# 17_FPGA_B12_B13_B14_B15.net
KiCad netlist of a schematic drawn in Altium Designer
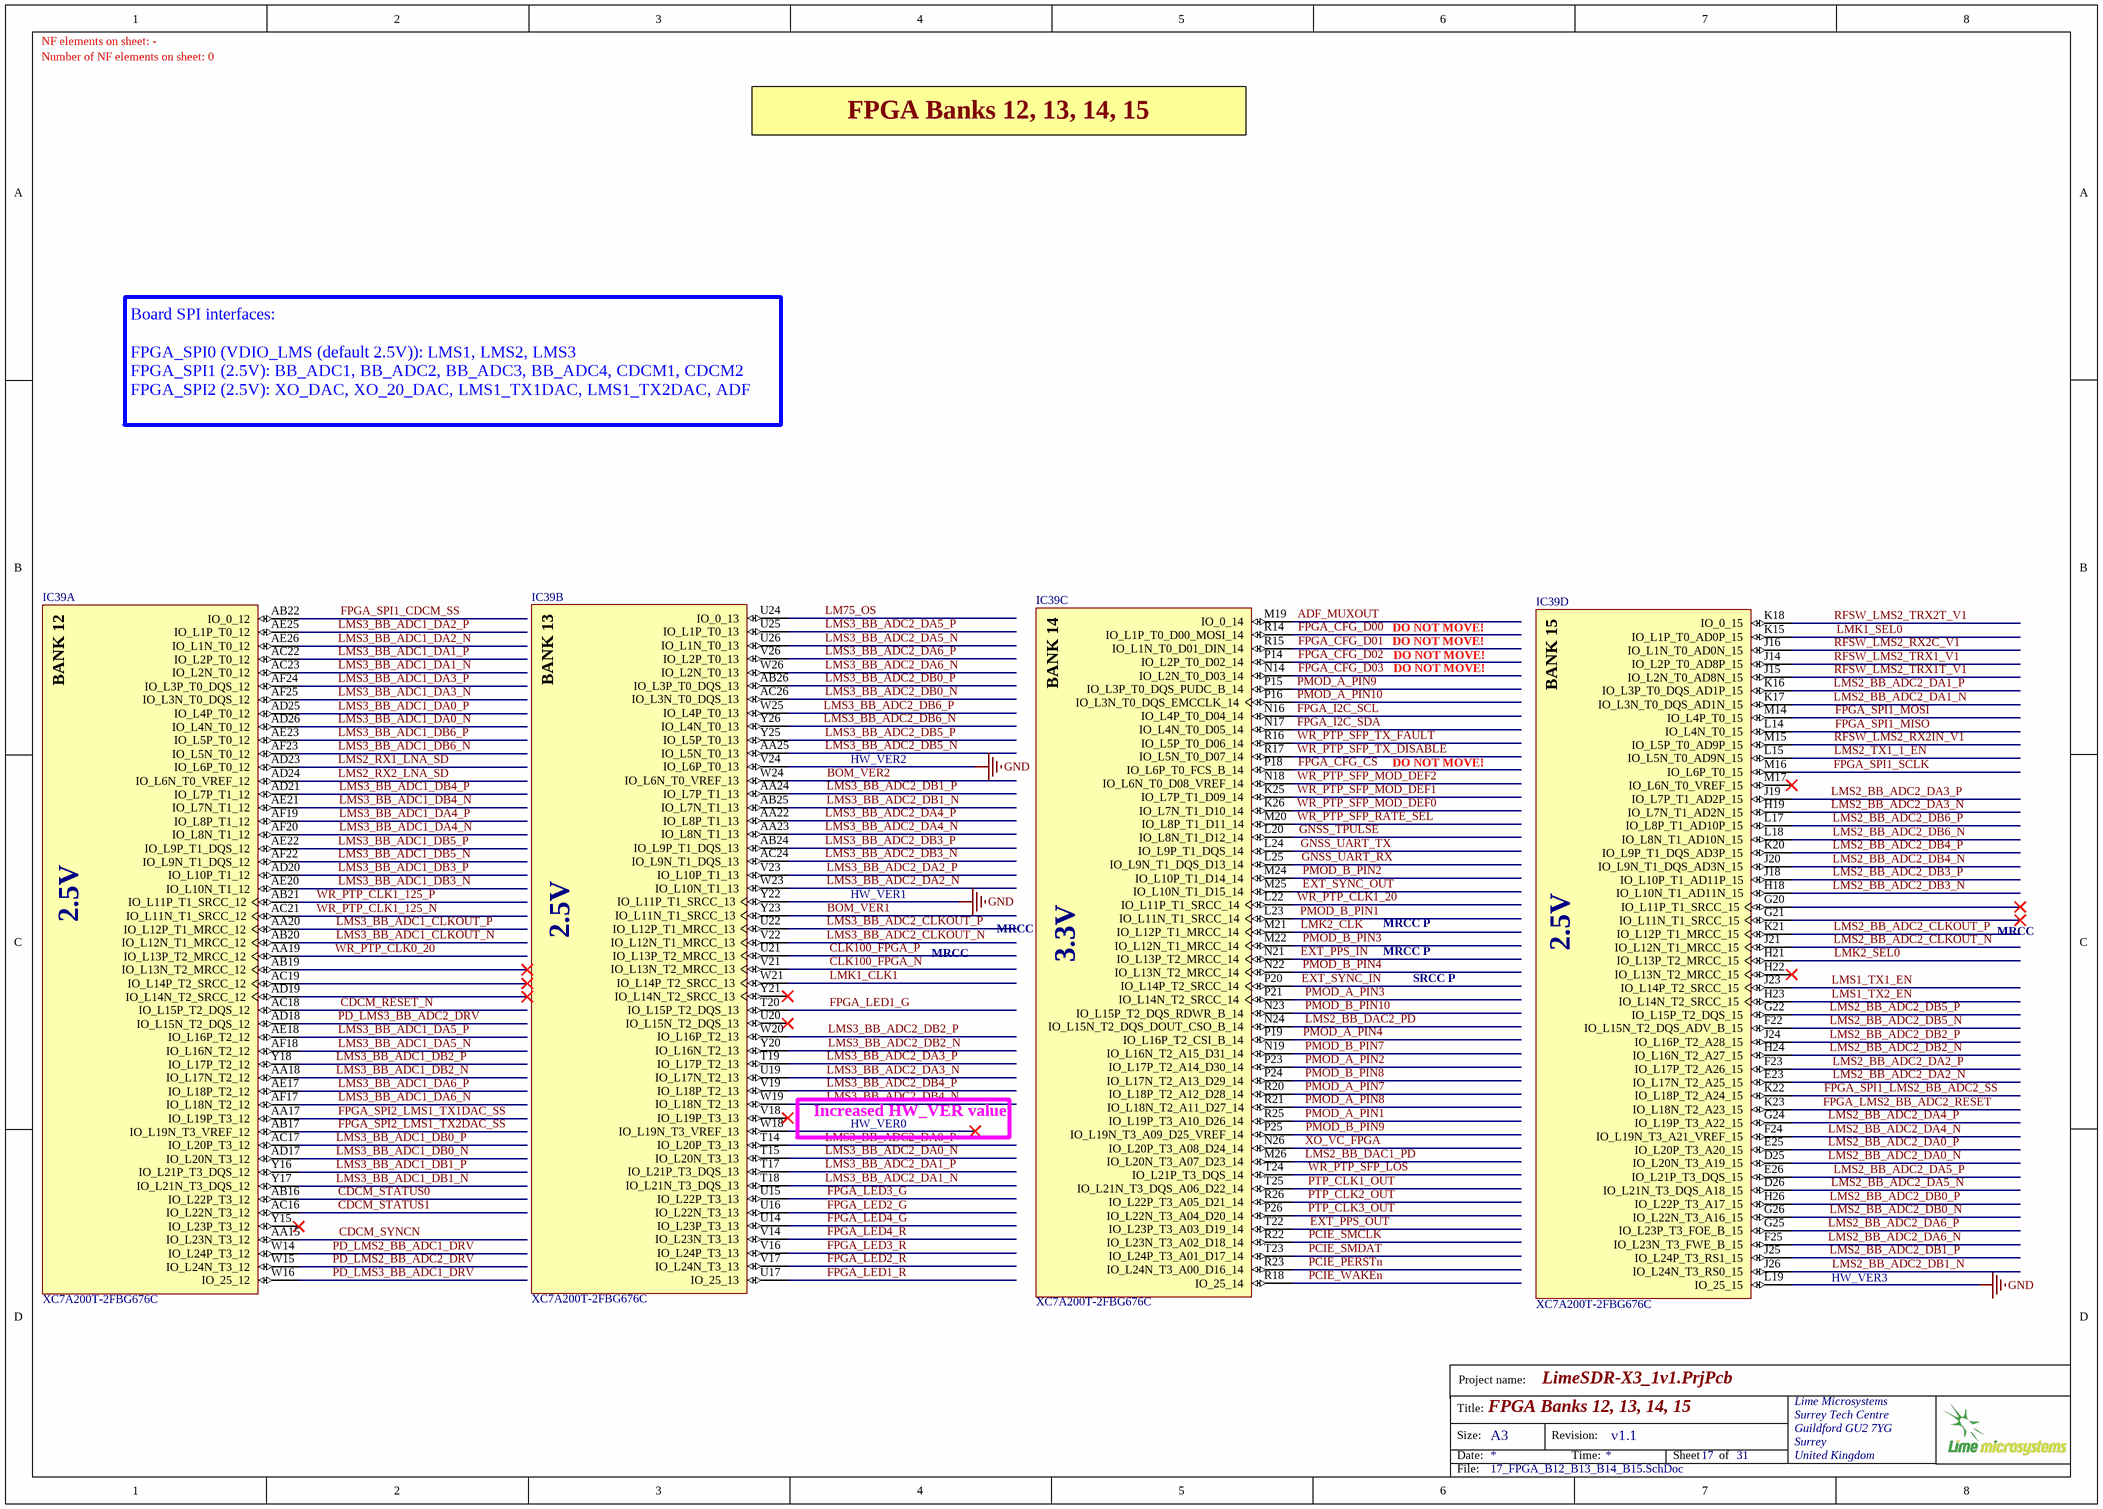
[diagram p0: 17_FPGA_B12_B13_B14_B15.SchDoc]

(export (version "E")
  (design (tool "Eeschema 10.0.6"))
  (components
    (comp (ref "IC39")
      (value "XC7A200T-2FBG676C")
      (footprint "XC7A200T-2FBG676C_FBG676")
      (description "Artix-7 FPGA, 400 User I/Os, 8 GTP, 676-Ball BGA, Speed Grade 2, Commercial Grade, Pb-Free")
      (fields (field (name "MANUFACTURER") "Xilinx"))
      (libsource (lib "LimeMicroAltiumLib_schLib_r02") (part "XC7A200T-2FBG676C"))
    )
  )
  (nets
    (net (code "1") (name "/ADF_MUXOUT") (class "Default")
      (node (ref "IC39") (pin "M19") (pinfunction "IO_0_14_M19") (pintype "bidirectional"))
    )
    (net (code "2") (name "/BOM_VER1") (class "Default")
      (node (ref "IC39") (pin "Y23") (pinfunction "IO_L11N_T1_SRCC_13_Y23") (pintype "bidirectional"))
    )
    (net (code "3") (name "/BOM_VER2") (class "Default")
      (node (ref "IC39") (pin "W24") (pinfunction "IO_L6N_T0_VREF_13_W24") (pintype "bidirectional"))
    )
    (net (code "4") (name "/CDCM_RESET_N") (class "Default")
      (node (ref "IC39") (pin "AC18") (pinfunction "IO_L15P_T2_DQS_12_AC18") (pintype "bidirectional"))
    )
    (net (code "5") (name "/CDCM_STATUS0") (class "Default")
      (node (ref "IC39") (pin "AB16") (pinfunction "IO_L22P_T3_12_AB16") (pintype "bidirectional"))
    )
    (net (code "6") (name "/CDCM_STATUS1") (class "Default")
      (node (ref "IC39") (pin "AC16") (pinfunction "IO_L22N_T3_12_AC16") (pintype "bidirectional"))
    )
    (net (code "7") (name "/CDCM_SYNCN") (class "Default")
      (node (ref "IC39") (pin "AA15") (pinfunction "IO_L23N_T3_12_AA15") (pintype "bidirectional"))
    )
    (net (code "8") (name "/CLK100_FPGA_N") (class "Default")
      (node (ref "IC39") (pin "V21") (pinfunction "IO_L13N_T2_MRCC_13_V21") (pintype "bidirectional"))
    )
    (net (code "9") (name "/CLK100_FPGA_P") (class "Default")
      (node (ref "IC39") (pin "U21") (pinfunction "IO_L13P_T2_MRCC_13_U21") (pintype "bidirectional"))
    )
    (net (code "10") (name "/EXT_PPS_IN") (class "Default")
      (node (ref "IC39") (pin "N21") (pinfunction "IO_L13P_T2_MRCC_14_N21") (pintype "bidirectional"))
    )
    (net (code "11") (name "/EXT_PPS_OUT") (class "Default")
      (node (ref "IC39") (pin "T22") (pinfunction "IO_L23P_T3_A03_D19_14_T22") (pintype "bidirectional"))
    )
    (net (code "12") (name "/EXT_SYNC_IN") (class "Default")
      (node (ref "IC39") (pin "P20") (pinfunction "IO_L14P_T2_SRCC_14_P20") (pintype "bidirectional"))
    )
    (net (code "13") (name "/EXT_SYNC_OUT") (class "Default")
      (node (ref "IC39") (pin "M25") (pinfunction "IO_L10N_T1_D15_14_M25") (pintype "bidirectional"))
    )
    (net (code "14") (name "/FPGA_CFG_CS") (class "Default")
      (node (ref "IC39") (pin "P18") (pinfunction "IO_L6P_T0_FCS_B_14_P18") (pintype "bidirectional"))
    )
    (net (code "15") (name "/FPGA_CFG_D00") (class "Default")
      (node (ref "IC39") (pin "R14") (pinfunction "IO_L1P_T0_D00_MOSI_14_R14") (pintype "bidirectional"))
    )
    (net (code "16") (name "/FPGA_CFG_D01") (class "Default")
      (node (ref "IC39") (pin "R15") (pinfunction "IO_L1N_T0_D01_DIN_14_R15") (pintype "bidirectional"))
    )
    (net (code "17") (name "/FPGA_CFG_D02") (class "Default")
      (node (ref "IC39") (pin "P14") (pinfunction "IO_L2P_T0_D02_14_P14") (pintype "bidirectional"))
    )
    (net (code "18") (name "/FPGA_CFG_D03") (class "Default")
      (node (ref "IC39") (pin "N14") (pinfunction "IO_L2N_T0_D03_14_N14") (pintype "bidirectional"))
    )
    (net (code "19") (name "/FPGA_I2C_SCL") (class "Default")
      (node (ref "IC39") (pin "N16") (pinfunction "IO_L4P_T0_D04_14_N16") (pintype "bidirectional"))
    )
    (net (code "20") (name "/FPGA_I2C_SDA") (class "Default")
      (node (ref "IC39") (pin "N17") (pinfunction "IO_L4N_T0_D05_14_N17") (pintype "bidirectional"))
    )
    (net (code "21") (name "/FPGA_LED1_G") (class "Default")
      (node (ref "IC39") (pin "T20") (pinfunction "IO_L15P_T2_DQS_13_T20") (pintype "bidirectional"))
    )
    (net (code "22") (name "/FPGA_LED1_R") (class "Default")
      (node (ref "IC39") (pin "U17") (pinfunction "IO_25_13_U17") (pintype "bidirectional"))
    )
    (net (code "23") (name "/FPGA_LED2_G") (class "Default")
      (node (ref "IC39") (pin "U16") (pinfunction "IO_L22N_T3_13_U16") (pintype "bidirectional"))
    )
    (net (code "24") (name "/FPGA_LED2_R") (class "Default")
      (node (ref "IC39") (pin "V17") (pinfunction "IO_L24N_T3_13_V17") (pintype "bidirectional"))
    )
    (net (code "25") (name "/FPGA_LED3_G") (class "Default")
      (node (ref "IC39") (pin "U15") (pinfunction "IO_L22P_T3_13_U15") (pintype "bidirectional"))
    )
    (net (code "26") (name "/FPGA_LED3_R") (class "Default")
      (node (ref "IC39") (pin "V16") (pinfunction "IO_L24P_T3_13_V16") (pintype "bidirectional"))
    )
    (net (code "27") (name "/FPGA_LED4_G") (class "Default")
      (node (ref "IC39") (pin "U14") (pinfunction "IO_L23P_T3_13_U14") (pintype "bidirectional"))
    )
    (net (code "28") (name "/FPGA_LED4_R") (class "Default")
      (node (ref "IC39") (pin "V14") (pinfunction "IO_L23N_T3_13_V14") (pintype "bidirectional"))
    )
    (net (code "29") (name "/FPGA_LMS2_BB_ADC2_RESET") (class "Default")
      (node (ref "IC39") (pin "K23") (pinfunction "IO_L18N_T2_A23_15_K23") (pintype "bidirectional"))
    )
    (net (code "30") (name "/FPGA_SPI1_CDCM_SS") (class "Default")
      (node (ref "IC39") (pin "AB22") (pinfunction "IO_0_12_AB22") (pintype "bidirectional"))
    )
    (net (code "31") (name "/FPGA_SPI1_LMS2_BB_ADC2_SS") (class "Default")
      (node (ref "IC39") (pin "K22") (pinfunction "IO_L18P_T2_A24_15_K22") (pintype "bidirectional"))
    )
    (net (code "32") (name "/FPGA_SPI1_MISO") (class "Default")
      (node (ref "IC39") (pin "L14") (pinfunction "IO_L4N_T0_15_L14") (pintype "bidirectional"))
    )
    (net (code "33") (name "/FPGA_SPI1_MOSI") (class "Default")
      (node (ref "IC39") (pin "M14") (pinfunction "IO_L4P_T0_15_M14") (pintype "bidirectional"))
    )
    (net (code "34") (name "/FPGA_SPI1_SCLK") (class "Default")
      (node (ref "IC39") (pin "M16") (pinfunction "IO_L6P_T0_15_M16") (pintype "bidirectional"))
    )
    (net (code "35") (name "/FPGA_SPI2_LMS1_TX1DAC_SS") (class "Default")
      (node (ref "IC39") (pin "AA17") (pinfunction "IO_L19P_T3_12_AA17") (pintype "bidirectional"))
    )
    (net (code "36") (name "/FPGA_SPI2_LMS1_TX2DAC_SS") (class "Default")
      (node (ref "IC39") (pin "AB17") (pinfunction "IO_L19N_T3_VREF_12_AB17") (pintype "bidirectional"))
    )
    (net (code "37") (name "/GNSS_TPULSE") (class "Default")
      (node (ref "IC39") (pin "L20") (pinfunction "IO_L8N_T1_D12_14_L20") (pintype "bidirectional"))
    )
    (net (code "38") (name "/GNSS_UART_RX") (class "Default")
      (node (ref "IC39") (pin "L25") (pinfunction "IO_L9N_T1_DQS_D13_14_L25") (pintype "bidirectional"))
    )
    (net (code "39") (name "/GNSS_UART_TX") (class "Default")
      (node (ref "IC39") (pin "L24") (pinfunction "IO_L9P_T1_DQS_14_L24") (pintype "bidirectional"))
    )
    (net (code "40") (name "/LM75_OS") (class "Default")
      (node (ref "IC39") (pin "U24") (pinfunction "IO_0_13_U24") (pintype "bidirectional"))
    )
    (net (code "41") (name "/LMK1_CLK1") (class "Default")
      (node (ref "IC39") (pin "W21") (pinfunction "IO_L14P_T2_SRCC_13_W21") (pintype "bidirectional"))
    )
    (net (code "42") (name "/LMK1_SEL0") (class "Default")
      (node (ref "IC39") (pin "K15") (pinfunction "IO_L1P_T0_AD0P_15_K15") (pintype "bidirectional"))
    )
    (net (code "43") (name "/LMK2_CLK") (class "Default")
      (node (ref "IC39") (pin "M21") (pinfunction "IO_L12P_T1_MRCC_14_M21") (pintype "bidirectional"))
    )
    (net (code "44") (name "/LMK2_SEL0") (class "Default")
      (node (ref "IC39") (pin "H21") (pinfunction "IO_L13P_T2_MRCC_15_H21") (pintype "bidirectional"))
    )
    (net (code "45") (name "/LMS1_TX1_EN") (class "Default")
      (node (ref "IC39") (pin "J23") (pinfunction "IO_L14P_T2_SRCC_15_J23") (pintype "bidirectional"))
    )
    (net (code "46") (name "/LMS1_TX2_EN") (class "Default")
      (node (ref "IC39") (pin "H23") (pinfunction "IO_L14N_T2_SRCC_15_H23") (pintype "bidirectional"))
    )
    (net (code "47") (name "/LMS2_BB_ADC2_CLKOUT_N") (class "Default")
      (node (ref "IC39") (pin "J21") (pinfunction "IO_L12N_T1_MRCC_15_J21") (pintype "bidirectional"))
    )
    (net (code "48") (name "/LMS2_BB_ADC2_CLKOUT_P") (class "Default")
      (node (ref "IC39") (pin "K21") (pinfunction "IO_L12P_T1_MRCC_15_K21") (pintype "bidirectional"))
    )
    (net (code "49") (name "/LMS2_BB_ADC2_DA0_N") (class "Default")
      (node (ref "IC39") (pin "D25") (pinfunction "IO_L20N_T3_A19_15_D25") (pintype "bidirectional"))
    )
    (net (code "50") (name "/LMS2_BB_ADC2_DA0_P") (class "Default")
      (node (ref "IC39") (pin "E25") (pinfunction "IO_L20P_T3_A20_15_E25") (pintype "bidirectional"))
    )
    (net (code "51") (name "/LMS2_BB_ADC2_DA1_N") (class "Default")
      (node (ref "IC39") (pin "K17") (pinfunction "IO_L3N_T0_DQS_AD1N_15_K17") (pintype "bidirectional"))
    )
    (net (code "52") (name "/LMS2_BB_ADC2_DA1_P") (class "Default")
      (node (ref "IC39") (pin "K16") (pinfunction "IO_L3P_T0_DQS_AD1P_15_K16") (pintype "bidirectional"))
    )
    (net (code "53") (name "/LMS2_BB_ADC2_DA2_N") (class "Default")
      (node (ref "IC39") (pin "E23") (pinfunction "IO_L17N_T2_A25_15_E23") (pintype "bidirectional"))
    )
    (net (code "54") (name "/LMS2_BB_ADC2_DA2_P") (class "Default")
      (node (ref "IC39") (pin "F23") (pinfunction "IO_L17P_T2_A26_15_F23") (pintype "bidirectional"))
    )
    (net (code "55") (name "/LMS2_BB_ADC2_DA3_N") (class "Default")
      (node (ref "IC39") (pin "H19") (pinfunction "IO_L7N_T1_AD2N_15_H19") (pintype "bidirectional"))
    )
    (net (code "56") (name "/LMS2_BB_ADC2_DA3_P") (class "Default")
      (node (ref "IC39") (pin "J19") (pinfunction "IO_L7P_T1_AD2P_15_J19") (pintype "bidirectional"))
    )
    (net (code "57") (name "/LMS2_BB_ADC2_DA4_N") (class "Default")
      (node (ref "IC39") (pin "F24") (pinfunction "IO_L19N_T3_A21_VREF_15_F24") (pintype "bidirectional"))
    )
    (net (code "58") (name "/LMS2_BB_ADC2_DA4_P") (class "Default")
      (node (ref "IC39") (pin "G24") (pinfunction "IO_L19P_T3_A22_15_G24") (pintype "bidirectional"))
    )
    (net (code "59") (name "/LMS2_BB_ADC2_DA5_N") (class "Default")
      (node (ref "IC39") (pin "D26") (pinfunction "IO_L21N_T3_DQS_A18_15_D26") (pintype "bidirectional"))
    )
    (net (code "60") (name "/LMS2_BB_ADC2_DA5_P") (class "Default")
      (node (ref "IC39") (pin "E26") (pinfunction "IO_L21P_T3_DQS_15_E26") (pintype "bidirectional"))
    )
    (net (code "61") (name "/LMS2_BB_ADC2_DA6_N") (class "Default")
      (node (ref "IC39") (pin "F25") (pinfunction "IO_L23N_T3_FWE_B_15_F25") (pintype "bidirectional"))
    )
    (net (code "62") (name "/LMS2_BB_ADC2_DA6_P") (class "Default")
      (node (ref "IC39") (pin "G25") (pinfunction "IO_L23P_T3_FOE_B_15_G25") (pintype "bidirectional"))
    )
    (net (code "63") (name "/LMS2_BB_ADC2_DB0_N") (class "Default")
      (node (ref "IC39") (pin "G26") (pinfunction "IO_L22N_T3_A16_15_G26") (pintype "bidirectional"))
    )
    (net (code "64") (name "/LMS2_BB_ADC2_DB0_P") (class "Default")
      (node (ref "IC39") (pin "H26") (pinfunction "IO_L22P_T3_A17_15_H26") (pintype "bidirectional"))
    )
    (net (code "65") (name "/LMS2_BB_ADC2_DB1_N") (class "Default")
      (node (ref "IC39") (pin "J26") (pinfunction "IO_L24N_T3_RS0_15_J26") (pintype "bidirectional"))
    )
    (net (code "66") (name "/LMS2_BB_ADC2_DB1_P") (class "Default")
      (node (ref "IC39") (pin "J25") (pinfunction "IO_L24P_T3_RS1_15_J25") (pintype "bidirectional"))
    )
    (net (code "67") (name "/LMS2_BB_ADC2_DB2_N") (class "Default")
      (node (ref "IC39") (pin "H24") (pinfunction "IO_L16N_T2_A27_15_H24") (pintype "bidirectional"))
    )
    (net (code "68") (name "/LMS2_BB_ADC2_DB2_P") (class "Default")
      (node (ref "IC39") (pin "J24") (pinfunction "IO_L16P_T2_A28_15_J24") (pintype "bidirectional"))
    )
    (net (code "69") (name "/LMS2_BB_ADC2_DB3_N") (class "Default")
      (node (ref "IC39") (pin "H18") (pinfunction "IO_L10N_T1_AD11N_15_H18") (pintype "bidirectional"))
    )
    (net (code "70") (name "/LMS2_BB_ADC2_DB3_P") (class "Default")
      (node (ref "IC39") (pin "J18") (pinfunction "IO_L10P_T1_AD11P_15_J18") (pintype "bidirectional"))
    )
    (net (code "71") (name "/LMS2_BB_ADC2_DB4_N") (class "Default")
      (node (ref "IC39") (pin "J20") (pinfunction "IO_L9N_T1_DQS_AD3N_15_J20") (pintype "bidirectional"))
    )
    (net (code "72") (name "/LMS2_BB_ADC2_DB4_P") (class "Default")
      (node (ref "IC39") (pin "K20") (pinfunction "IO_L9P_T1_DQS_AD3P_15_K20") (pintype "bidirectional"))
    )
    (net (code "73") (name "/LMS2_BB_ADC2_DB5_N") (class "Default")
      (node (ref "IC39") (pin "F22") (pinfunction "IO_L15N_T2_DQS_ADV_B_15_F22") (pintype "bidirectional"))
    )
    (net (code "74") (name "/LMS2_BB_ADC2_DB5_P") (class "Default")
      (node (ref "IC39") (pin "G22") (pinfunction "IO_L15P_T2_DQS_15_G22") (pintype "bidirectional"))
    )
    (net (code "75") (name "/LMS2_BB_ADC2_DB6_N") (class "Default")
      (node (ref "IC39") (pin "L18") (pinfunction "IO_L8N_T1_AD10N_15_L18") (pintype "bidirectional"))
    )
    (net (code "76") (name "/LMS2_BB_ADC2_DB6_P") (class "Default")
      (node (ref "IC39") (pin "L17") (pinfunction "IO_L8P_T1_AD10P_15_L17") (pintype "bidirectional"))
    )
    (net (code "77") (name "/LMS2_BB_DAC1_PD") (class "Default")
      (node (ref "IC39") (pin "M26") (pinfunction "IO_L20N_T3_A07_D23_14_M26") (pintype "bidirectional"))
    )
    (net (code "78") (name "/LMS2_BB_DAC2_PD") (class "Default")
      (node (ref "IC39") (pin "N24") (pinfunction "IO_L15N_T2_DQS_DOUT_CSO_B_14_N24") (pintype "bidirectional"))
    )
    (net (code "79") (name "/LMS2_RX1_LNA_SD") (class "Default")
      (node (ref "IC39") (pin "AD23") (pinfunction "IO_L6P_T0_12_AD23") (pintype "bidirectional"))
    )
    (net (code "80") (name "/LMS2_RX2_LNA_SD") (class "Default")
      (node (ref "IC39") (pin "AD24") (pinfunction "IO_L6N_T0_VREF_12_AD24") (pintype "bidirectional"))
    )
    (net (code "81") (name "/LMS2_TX1_1_EN") (class "Default")
      (node (ref "IC39") (pin "L15") (pinfunction "IO_L5N_T0_AD9N_15_L15") (pintype "bidirectional"))
    )
    (net (code "82") (name "/LMS3_BB_ADC1_CLKOUT_N") (class "Default")
      (node (ref "IC39") (pin "AB20") (pinfunction "IO_L12N_T1_MRCC_12_AB20") (pintype "bidirectional"))
    )
    (net (code "83") (name "/LMS3_BB_ADC1_CLKOUT_P") (class "Default")
      (node (ref "IC39") (pin "AA20") (pinfunction "IO_L12P_T1_MRCC_12_AA20") (pintype "bidirectional"))
    )
    (net (code "84") (name "/LMS3_BB_ADC1_DA0_N") (class "Default")
      (node (ref "IC39") (pin "AD26") (pinfunction "IO_L4N_T0_12_AD26") (pintype "bidirectional"))
    )
    (net (code "85") (name "/LMS3_BB_ADC1_DA0_P") (class "Default")
      (node (ref "IC39") (pin "AD25") (pinfunction "IO_L4P_T0_12_AD25") (pintype "bidirectional"))
    )
    (net (code "86") (name "/LMS3_BB_ADC1_DA1_N") (class "Default")
      (node (ref "IC39") (pin "AC23") (pinfunction "IO_L2N_T0_12_AC23") (pintype "bidirectional"))
    )
    (net (code "87") (name "/LMS3_BB_ADC1_DA1_P") (class "Default")
      (node (ref "IC39") (pin "AC22") (pinfunction "IO_L2P_T0_12_AC22") (pintype "bidirectional"))
    )
    (net (code "88") (name "/LMS3_BB_ADC1_DA2_N") (class "Default")
      (node (ref "IC39") (pin "AE26") (pinfunction "IO_L1N_T0_12_AE26") (pintype "bidirectional"))
    )
    (net (code "89") (name "/LMS3_BB_ADC1_DA2_P") (class "Default")
      (node (ref "IC39") (pin "AE25") (pinfunction "IO_L1P_T0_12_AE25") (pintype "bidirectional"))
    )
    (net (code "90") (name "/LMS3_BB_ADC1_DA3_N") (class "Default")
      (node (ref "IC39") (pin "AF25") (pinfunction "IO_L3N_T0_DQS_12_AF25") (pintype "bidirectional"))
    )
    (net (code "91") (name "/LMS3_BB_ADC1_DA3_P") (class "Default")
      (node (ref "IC39") (pin "AF24") (pinfunction "IO_L3P_T0_DQS_12_AF24") (pintype "bidirectional"))
    )
    (net (code "92") (name "/LMS3_BB_ADC1_DA4_N") (class "Default")
      (node (ref "IC39") (pin "AF20") (pinfunction "IO_L8N_T1_12_AF20") (pintype "bidirectional"))
    )
    (net (code "93") (name "/LMS3_BB_ADC1_DA4_P") (class "Default")
      (node (ref "IC39") (pin "AF19") (pinfunction "IO_L8P_T1_12_AF19") (pintype "bidirectional"))
    )
    (net (code "94") (name "/LMS3_BB_ADC1_DA5_N") (class "Default")
      (node (ref "IC39") (pin "AF18") (pinfunction "IO_L16N_T2_12_AF18") (pintype "bidirectional"))
    )
    (net (code "95") (name "/LMS3_BB_ADC1_DA5_P") (class "Default")
      (node (ref "IC39") (pin "AE18") (pinfunction "IO_L16P_T2_12_AE18") (pintype "bidirectional"))
    )
    (net (code "96") (name "/LMS3_BB_ADC1_DA6_N") (class "Default")
      (node (ref "IC39") (pin "AF17") (pinfunction "IO_L18N_T2_12_AF17") (pintype "bidirectional"))
    )
    (net (code "97") (name "/LMS3_BB_ADC1_DA6_P") (class "Default")
      (node (ref "IC39") (pin "AE17") (pinfunction "IO_L18P_T2_12_AE17") (pintype "bidirectional"))
    )
    (net (code "98") (name "/LMS3_BB_ADC1_DB0_N") (class "Default")
      (node (ref "IC39") (pin "AD17") (pinfunction "IO_L20N_T3_12_AD17") (pintype "bidirectional"))
    )
    (net (code "99") (name "/LMS3_BB_ADC1_DB0_P") (class "Default")
      (node (ref "IC39") (pin "AC17") (pinfunction "IO_L20P_T3_12_AC17") (pintype "bidirectional"))
    )
    (net (code "100") (name "/LMS3_BB_ADC1_DB1_N") (class "Default")
      (node (ref "IC39") (pin "Y17") (pinfunction "IO_L21N_T3_DQS_12_Y17") (pintype "bidirectional"))
    )
    (net (code "101") (name "/LMS3_BB_ADC1_DB1_P") (class "Default")
      (node (ref "IC39") (pin "Y16") (pinfunction "IO_L21P_T3_DQS_12_Y16") (pintype "bidirectional"))
    )
    (net (code "102") (name "/LMS3_BB_ADC1_DB2_N") (class "Default")
      (node (ref "IC39") (pin "AA18") (pinfunction "IO_L17N_T2_12_AA18") (pintype "bidirectional"))
    )
    (net (code "103") (name "/LMS3_BB_ADC1_DB2_P") (class "Default")
      (node (ref "IC39") (pin "Y18") (pinfunction "IO_L17P_T2_12_Y18") (pintype "bidirectional"))
    )
    (net (code "104") (name "/LMS3_BB_ADC1_DB3_N") (class "Default")
      (node (ref "IC39") (pin "AE20") (pinfunction "IO_L10N_T1_12_AE20") (pintype "bidirectional"))
    )
    (net (code "105") (name "/LMS3_BB_ADC1_DB3_P") (class "Default")
      (node (ref "IC39") (pin "AD20") (pinfunction "IO_L10P_T1_12_AD20") (pintype "bidirectional"))
    )
    (net (code "106") (name "/LMS3_BB_ADC1_DB4_N") (class "Default")
      (node (ref "IC39") (pin "AE21") (pinfunction "IO_L7N_T1_12_AE21") (pintype "bidirectional"))
    )
    (net (code "107") (name "/LMS3_BB_ADC1_DB4_P") (class "Default")
      (node (ref "IC39") (pin "AD21") (pinfunction "IO_L7P_T1_12_AD21") (pintype "bidirectional"))
    )
    (net (code "108") (name "/LMS3_BB_ADC1_DB5_N") (class "Default")
      (node (ref "IC39") (pin "AF22") (pinfunction "IO_L9N_T1_DQS_12_AF22") (pintype "bidirectional"))
    )
    (net (code "109") (name "/LMS3_BB_ADC1_DB5_P") (class "Default")
      (node (ref "IC39") (pin "AE22") (pinfunction "IO_L9P_T1_DQS_12_AE22") (pintype "bidirectional"))
    )
    (net (code "110") (name "/LMS3_BB_ADC1_DB6_N") (class "Default")
      (node (ref "IC39") (pin "AF23") (pinfunction "IO_L5N_T0_12_AF23") (pintype "bidirectional"))
    )
    (net (code "111") (name "/LMS3_BB_ADC1_DB6_P") (class "Default")
      (node (ref "IC39") (pin "AE23") (pinfunction "IO_L5P_T0_12_AE23") (pintype "bidirectional"))
    )
    (net (code "112") (name "/LMS3_BB_ADC2_CLKOUT_N") (class "Default")
      (node (ref "IC39") (pin "V22") (pinfunction "IO_L12N_T1_MRCC_13_V22") (pintype "bidirectional"))
    )
    (net (code "113") (name "/LMS3_BB_ADC2_CLKOUT_P") (class "Default")
      (node (ref "IC39") (pin "U22") (pinfunction "IO_L12P_T1_MRCC_13_U22") (pintype "bidirectional"))
    )
    (net (code "114") (name "/LMS3_BB_ADC2_DA0_N") (class "Default")
      (node (ref "IC39") (pin "T15") (pinfunction "IO_L20N_T3_13_T15") (pintype "bidirectional"))
    )
    (net (code "115") (name "/LMS3_BB_ADC2_DA0_P") (class "Default")
      (node (ref "IC39") (pin "T14") (pinfunction "IO_L20P_T3_13_T14") (pintype "bidirectional"))
    )
    (net (code "116") (name "/LMS3_BB_ADC2_DA1_N") (class "Default")
      (node (ref "IC39") (pin "T18") (pinfunction "IO_L21N_T3_DQS_13_T18") (pintype "bidirectional"))
    )
    (net (code "117") (name "/LMS3_BB_ADC2_DA1_P") (class "Default")
      (node (ref "IC39") (pin "T17") (pinfunction "IO_L21P_T3_DQS_13_T17") (pintype "bidirectional"))
    )
    (net (code "118") (name "/LMS3_BB_ADC2_DA2_N") (class "Default")
      (node (ref "IC39") (pin "W23") (pinfunction "IO_L10N_T1_13_W23") (pintype "bidirectional"))
    )
    (net (code "119") (name "/LMS3_BB_ADC2_DA2_P") (class "Default")
      (node (ref "IC39") (pin "V23") (pinfunction "IO_L10P_T1_13_V23") (pintype "bidirectional"))
    )
    (net (code "120") (name "/LMS3_BB_ADC2_DA3_N") (class "Default")
      (node (ref "IC39") (pin "U19") (pinfunction "IO_L17N_T2_13_U19") (pintype "bidirectional"))
    )
    (net (code "121") (name "/LMS3_BB_ADC2_DA3_P") (class "Default")
      (node (ref "IC39") (pin "T19") (pinfunction "IO_L17P_T2_13_T19") (pintype "bidirectional"))
    )
    (net (code "122") (name "/LMS3_BB_ADC2_DA4_N") (class "Default")
      (node (ref "IC39") (pin "AA23") (pinfunction "IO_L8N_T1_13_AA23") (pintype "bidirectional"))
    )
    (net (code "123") (name "/LMS3_BB_ADC2_DA4_P") (class "Default")
      (node (ref "IC39") (pin "AA22") (pinfunction "IO_L8P_T1_13_AA22") (pintype "bidirectional"))
    )
    (net (code "124") (name "/LMS3_BB_ADC2_DA5_N") (class "Default")
      (node (ref "IC39") (pin "U26") (pinfunction "IO_L1N_T0_13_U26") (pintype "bidirectional"))
    )
    (net (code "125") (name "/LMS3_BB_ADC2_DA5_P") (class "Default")
      (node (ref "IC39") (pin "U25") (pinfunction "IO_L1P_T0_13_U25") (pintype "bidirectional"))
    )
    (net (code "126") (name "/LMS3_BB_ADC2_DA6_N") (class "Default")
      (node (ref "IC39") (pin "W26") (pinfunction "IO_L2N_T0_13_W26") (pintype "bidirectional"))
    )
    (net (code "127") (name "/LMS3_BB_ADC2_DA6_P") (class "Default")
      (node (ref "IC39") (pin "V26") (pinfunction "IO_L2P_T0_13_V26") (pintype "bidirectional"))
    )
    (net (code "128") (name "/LMS3_BB_ADC2_DB0_N") (class "Default")
      (node (ref "IC39") (pin "AC26") (pinfunction "IO_L3N_T0_DQS_13_AC26") (pintype "bidirectional"))
    )
    (net (code "129") (name "/LMS3_BB_ADC2_DB0_P") (class "Default")
      (node (ref "IC39") (pin "AB26") (pinfunction "IO_L3P_T0_DQS_13_AB26") (pintype "bidirectional"))
    )
    (net (code "130") (name "/LMS3_BB_ADC2_DB1_N") (class "Default")
      (node (ref "IC39") (pin "AB25") (pinfunction "IO_L7N_T1_13_AB25") (pintype "bidirectional"))
    )
    (net (code "131") (name "/LMS3_BB_ADC2_DB1_P") (class "Default")
      (node (ref "IC39") (pin "AA24") (pinfunction "IO_L7P_T1_13_AA24") (pintype "bidirectional"))
    )
    (net (code "132") (name "/LMS3_BB_ADC2_DB2_N") (class "Default")
      (node (ref "IC39") (pin "Y20") (pinfunction "IO_L16N_T2_13_Y20") (pintype "bidirectional"))
    )
    (net (code "133") (name "/LMS3_BB_ADC2_DB2_P") (class "Default")
      (node (ref "IC39") (pin "W20") (pinfunction "IO_L16P_T2_13_W20") (pintype "bidirectional"))
    )
    (net (code "134") (name "/LMS3_BB_ADC2_DB3_N") (class "Default")
      (node (ref "IC39") (pin "AC24") (pinfunction "IO_L9N_T1_DQS_13_AC24") (pintype "bidirectional"))
    )
    (net (code "135") (name "/LMS3_BB_ADC2_DB3_P") (class "Default")
      (node (ref "IC39") (pin "AB24") (pinfunction "IO_L9P_T1_DQS_13_AB24") (pintype "bidirectional"))
    )
    (net (code "136") (name "/LMS3_BB_ADC2_DB4_N") (class "Default")
      (node (ref "IC39") (pin "W19") (pinfunction "IO_L18N_T2_13_W19") (pintype "bidirectional"))
    )
    (net (code "137") (name "/LMS3_BB_ADC2_DB4_P") (class "Default")
      (node (ref "IC39") (pin "V19") (pinfunction "IO_L18P_T2_13_V19") (pintype "bidirectional"))
    )
    (net (code "138") (name "/LMS3_BB_ADC2_DB5_N") (class "Default")
      (node (ref "IC39") (pin "AA25") (pinfunction "IO_L5N_T0_13_AA25") (pintype "bidirectional"))
    )
    (net (code "139") (name "/LMS3_BB_ADC2_DB5_P") (class "Default")
      (node (ref "IC39") (pin "Y25") (pinfunction "IO_L5P_T0_13_Y25") (pintype "bidirectional"))
    )
    (net (code "140") (name "/LMS3_BB_ADC2_DB6_N") (class "Default")
      (node (ref "IC39") (pin "Y26") (pinfunction "IO_L4N_T0_13_Y26") (pintype "bidirectional"))
    )
    (net (code "141") (name "/LMS3_BB_ADC2_DB6_P") (class "Default")
      (node (ref "IC39") (pin "W25") (pinfunction "IO_L4P_T0_13_W25") (pintype "bidirectional"))
    )
    (net (code "142") (name "/PCIE_PERSTn") (class "Default")
      (node (ref "IC39") (pin "R23") (pinfunction "IO_L24N_T3_A00_D16_14_R23") (pintype "bidirectional"))
    )
    (net (code "143") (name "/PCIE_SMCLK") (class "Default")
      (node (ref "IC39") (pin "R22") (pinfunction "IO_L23N_T3_A02_D18_14_R22") (pintype "bidirectional"))
    )
    (net (code "144") (name "/PCIE_SMDAT") (class "Default")
      (node (ref "IC39") (pin "T23") (pinfunction "IO_L24P_T3_A01_D17_14_T23") (pintype "bidirectional"))
    )
    (net (code "145") (name "/PCIE_WAKEn") (class "Default")
      (node (ref "IC39") (pin "R18") (pinfunction "IO_25_14_R18") (pintype "bidirectional"))
    )
    (net (code "146") (name "/PD_LMS2_BB_ADC1_DRV") (class "Default")
      (node (ref "IC39") (pin "W14") (pinfunction "IO_L24P_T3_12_W14") (pintype "bidirectional"))
    )
    (net (code "147") (name "/PD_LMS2_BB_ADC2_DRV") (class "Default")
      (node (ref "IC39") (pin "W15") (pinfunction "IO_L24N_T3_12_W15") (pintype "bidirectional"))
    )
    (net (code "148") (name "/PD_LMS3_BB_ADC1_DRV") (class "Default")
      (node (ref "IC39") (pin "W16") (pinfunction "IO_25_12_W16") (pintype "bidirectional"))
    )
    (net (code "149") (name "/PD_LMS3_BB_ADC2_DRV") (class "Default")
      (node (ref "IC39") (pin "AD18") (pinfunction "IO_L15N_T2_DQS_12_AD18") (pintype "bidirectional"))
    )
    (net (code "150") (name "/PMOD_A_PIN1") (class "Default")
      (node (ref "IC39") (pin "R25") (pinfunction "IO_L19P_T3_A10_D26_14_R25") (pintype "bidirectional"))
    )
    (net (code "151") (name "/PMOD_A_PIN2") (class "Default")
      (node (ref "IC39") (pin "P23") (pinfunction "IO_L17P_T2_A14_D30_14_P23") (pintype "bidirectional"))
    )
    (net (code "152") (name "/PMOD_A_PIN3") (class "Default")
      (node (ref "IC39") (pin "P21") (pinfunction "IO_L14N_T2_SRCC_14_P21") (pintype "bidirectional"))
    )
    (net (code "153") (name "/PMOD_A_PIN4") (class "Default")
      (node (ref "IC39") (pin "P19") (pinfunction "IO_L16P_T2_CSI_B_14_P19") (pintype "bidirectional"))
    )
    (net (code "154") (name "/PMOD_A_PIN7") (class "Default")
      (node (ref "IC39") (pin "R20") (pinfunction "IO_L18P_T2_A12_D28_14_R20") (pintype "bidirectional"))
    )
    (net (code "155") (name "/PMOD_A_PIN8") (class "Default")
      (node (ref "IC39") (pin "R21") (pinfunction "IO_L18N_T2_A11_D27_14_R21") (pintype "bidirectional"))
    )
    (net (code "156") (name "/PMOD_A_PIN9") (class "Default")
      (node (ref "IC39") (pin "P15") (pinfunction "IO_L3P_T0_DQS_PUDC_B_14_P15") (pintype "bidirectional"))
    )
    (net (code "157") (name "/PMOD_A_PIN10") (class "Default")
      (node (ref "IC39") (pin "P16") (pinfunction "IO_L3N_T0_DQS_EMCCLK_14_P16") (pintype "bidirectional"))
    )
    (net (code "158") (name "/PMOD_B_PIN1") (class "Default")
      (node (ref "IC39") (pin "L23") (pinfunction "IO_L11N_T1_SRCC_14_L23") (pintype "bidirectional"))
    )
    (net (code "159") (name "/PMOD_B_PIN2") (class "Default")
      (node (ref "IC39") (pin "M24") (pinfunction "IO_L10P_T1_D14_14_M24") (pintype "bidirectional"))
    )
    (net (code "160") (name "/PMOD_B_PIN3") (class "Default")
      (node (ref "IC39") (pin "M22") (pinfunction "IO_L12N_T1_MRCC_14_M22") (pintype "bidirectional"))
    )
    (net (code "161") (name "/PMOD_B_PIN4") (class "Default")
      (node (ref "IC39") (pin "N22") (pinfunction "IO_L13N_T2_MRCC_14_N22") (pintype "bidirectional"))
    )
    (net (code "162") (name "/PMOD_B_PIN7") (class "Default")
      (node (ref "IC39") (pin "N19") (pinfunction "IO_L16N_T2_A15_D31_14_N19") (pintype "bidirectional"))
    )
    (net (code "163") (name "/PMOD_B_PIN8") (class "Default")
      (node (ref "IC39") (pin "P24") (pinfunction "IO_L17N_T2_A13_D29_14_P24") (pintype "bidirectional"))
    )
    (net (code "164") (name "/PMOD_B_PIN9") (class "Default")
      (node (ref "IC39") (pin "P25") (pinfunction "IO_L19N_T3_A09_D25_VREF_14_P25") (pintype "bidirectional"))
    )
    (net (code "165") (name "/PMOD_B_PIN10") (class "Default")
      (node (ref "IC39") (pin "N23") (pinfunction "IO_L15P_T2_DQS_RDWR_B_14_N23") (pintype "bidirectional"))
    )
    (net (code "166") (name "/PTP_CLK1_OUT") (class "Default")
      (node (ref "IC39") (pin "T25") (pinfunction "IO_L21N_T3_DQS_A06_D22_14_T25") (pintype "bidirectional"))
    )
    (net (code "167") (name "/PTP_CLK2_OUT") (class "Default")
      (node (ref "IC39") (pin "R26") (pinfunction "IO_L22P_T3_A05_D21_14_R26") (pintype "bidirectional"))
    )
    (net (code "168") (name "/PTP_CLK3_OUT") (class "Default")
      (node (ref "IC39") (pin "P26") (pinfunction "IO_L22N_T3_A04_D20_14_P26") (pintype "bidirectional"))
    )
    (net (code "169") (name "/RFSW_LMS2_RX2C_V1") (class "Default")
      (node (ref "IC39") (pin "J16") (pinfunction "IO_L1N_T0_AD0N_15_J16") (pintype "bidirectional"))
    )
    (net (code "170") (name "/RFSW_LMS2_RX2IN_V1") (class "Default")
      (node (ref "IC39") (pin "M15") (pinfunction "IO_L5P_T0_AD9P_15_M15") (pintype "bidirectional"))
    )
    (net (code "171") (name "/RFSW_LMS2_TRX1T_V1") (class "Default")
      (node (ref "IC39") (pin "J15") (pinfunction "IO_L2N_T0_AD8N_15_J15") (pintype "bidirectional"))
    )
    (net (code "172") (name "/RFSW_LMS2_TRX1_V1") (class "Default")
      (node (ref "IC39") (pin "J14") (pinfunction "IO_L2P_T0_AD8P_15_J14") (pintype "bidirectional"))
    )
    (net (code "173") (name "/RFSW_LMS2_TRX2T_V1") (class "Default")
      (node (ref "IC39") (pin "K18") (pinfunction "IO_0_15_K18") (pintype "bidirectional"))
    )
    (net (code "174") (name "/WR_PTP_CLK0_20") (class "Default")
      (node (ref "IC39") (pin "AA19") (pinfunction "IO_L13P_T2_MRCC_12_AA19") (pintype "bidirectional"))
    )
    (net (code "175") (name "/WR_PTP_CLK1_20") (class "Default")
      (node (ref "IC39") (pin "L22") (pinfunction "IO_L11P_T1_SRCC_14_L22") (pintype "bidirectional"))
    )
    (net (code "176") (name "/WR_PTP_CLK1_125_N") (class "Default")
      (node (ref "IC39") (pin "AC21") (pinfunction "IO_L11N_T1_SRCC_12_AC21") (pintype "bidirectional"))
    )
    (net (code "177") (name "/WR_PTP_CLK1_125_P") (class "Default")
      (node (ref "IC39") (pin "AB21") (pinfunction "IO_L11P_T1_SRCC_12_AB21") (pintype "bidirectional"))
    )
    (net (code "178") (name "/WR_PTP_SFP_LOS") (class "Default")
      (node (ref "IC39") (pin "T24") (pinfunction "IO_L21P_T3_DQS_14_T24") (pintype "bidirectional"))
    )
    (net (code "179") (name "/WR_PTP_SFP_MOD_DEF0") (class "Default")
      (node (ref "IC39") (pin "K26") (pinfunction "IO_L7N_T1_D10_14_K26") (pintype "bidirectional"))
    )
    (net (code "180") (name "/WR_PTP_SFP_MOD_DEF1") (class "Default")
      (node (ref "IC39") (pin "K25") (pinfunction "IO_L7P_T1_D09_14_K25") (pintype "bidirectional"))
    )
    (net (code "181") (name "/WR_PTP_SFP_MOD_DEF2") (class "Default")
      (node (ref "IC39") (pin "N18") (pinfunction "IO_L6N_T0_D08_VREF_14_N18") (pintype "bidirectional"))
    )
    (net (code "182") (name "/WR_PTP_SFP_RATE_SEL") (class "Default")
      (node (ref "IC39") (pin "M20") (pinfunction "IO_L8P_T1_D11_14_M20") (pintype "bidirectional"))
    )
    (net (code "183") (name "/WR_PTP_SFP_TX_DISABLE") (class "Default")
      (node (ref "IC39") (pin "R17") (pinfunction "IO_L5N_T0_D07_14_R17") (pintype "bidirectional"))
    )
    (net (code "184") (name "/WR_PTP_SFP_TX_FAULT") (class "Default")
      (node (ref "IC39") (pin "R16") (pinfunction "IO_L5P_T0_D06_14_R16") (pintype "bidirectional"))
    )
    (net (code "185") (name "/XO_VC_FPGA") (class "Default")
      (node (ref "IC39") (pin "N26") (pinfunction "IO_L20P_T3_A08_D24_14_N26") (pintype "bidirectional"))
    )
    (net (code "186") (name "GND") (class "Default")
      (node (ref "IC39") (pin "L19") (pinfunction "IO_25_15_L19") (pintype "bidirectional"))
      (node (ref "IC39") (pin "V24") (pinfunction "IO_L6P_T0_13_V24") (pintype "bidirectional"))
      (node (ref "IC39") (pin "Y22") (pinfunction "IO_L11P_T1_SRCC_13_Y22") (pintype "bidirectional"))
    )
    (net (code "187") (name "unconnected-(IC39A-IO_L13N_T2_MRCC_12-PadAB19)") (class "Default")
      (node (ref "IC39") (pin "AB19") (pinfunction "IO_L13N_T2_MRCC_12_AB19") (pintype "bidirectional+no_connect"))
    )
    (net (code "188") (name "unconnected-(IC39A-IO_L14N_T2_SRCC_12-PadAD19)") (class "Default")
      (node (ref "IC39") (pin "AD19") (pinfunction "IO_L14N_T2_SRCC_12_AD19") (pintype "bidirectional+no_connect"))
    )
    (net (code "189") (name "unconnected-(IC39A-IO_L14P_T2_SRCC_12-PadAC19)") (class "Default")
      (node (ref "IC39") (pin "AC19") (pinfunction "IO_L14P_T2_SRCC_12_AC19") (pintype "bidirectional+no_connect"))
    )
    (net (code "190") (name "unconnected-(IC39A-IO_L23P_T3_12-PadY15)") (class "Default")
      (node (ref "IC39") (pin "Y15") (pinfunction "IO_L23P_T3_12_Y15") (pintype "bidirectional+no_connect"))
    )
    (net (code "191") (name "unconnected-(IC39B-IO_L14N_T2_SRCC_13-PadY21)") (class "Default")
      (node (ref "IC39") (pin "Y21") (pinfunction "IO_L14N_T2_SRCC_13_Y21") (pintype "bidirectional+no_connect"))
    )
    (net (code "192") (name "unconnected-(IC39B-IO_L15N_T2_DQS_13-PadU20)") (class "Default")
      (node (ref "IC39") (pin "U20") (pinfunction "IO_L15N_T2_DQS_13_U20") (pintype "bidirectional+no_connect"))
    )
    (net (code "193") (name "unconnected-(IC39B-IO_L19N_T3_VREF_13-PadW18)") (class "Default")
      (node (ref "IC39") (pin "W18") (pinfunction "IO_L19N_T3_VREF_13_W18") (pintype "bidirectional+no_connect"))
    )
    (net (code "194") (name "unconnected-(IC39B-IO_L19P_T3_13-PadV18)") (class "Default")
      (node (ref "IC39") (pin "V18") (pinfunction "IO_L19P_T3_13_V18") (pintype "bidirectional+no_connect"))
    )
    (net (code "195") (name "unconnected-(IC39D-IO_L6N_T0_VREF_15-PadM17)") (class "Default")
      (node (ref "IC39") (pin "M17") (pinfunction "IO_L6N_T0_VREF_15_M17") (pintype "bidirectional+no_connect"))
    )
    (net (code "196") (name "unconnected-(IC39D-IO_L11N_T1_SRCC_15-PadG21)") (class "Default")
      (node (ref "IC39") (pin "G21") (pinfunction "IO_L11N_T1_SRCC_15_G21") (pintype "bidirectional+no_connect"))
    )
    (net (code "197") (name "unconnected-(IC39D-IO_L11P_T1_SRCC_15-PadG20)") (class "Default")
      (node (ref "IC39") (pin "G20") (pinfunction "IO_L11P_T1_SRCC_15_G20") (pintype "bidirectional+no_connect"))
    )
    (net (code "198") (name "unconnected-(IC39D-IO_L13N_T2_MRCC_15-PadH22)") (class "Default")
      (node (ref "IC39") (pin "H22") (pinfunction "IO_L13N_T2_MRCC_15_H22") (pintype "bidirectional+no_connect"))
    )
  )
)
